# connectors.net
KiCad netlist of a schematic drawn in Altium Designer
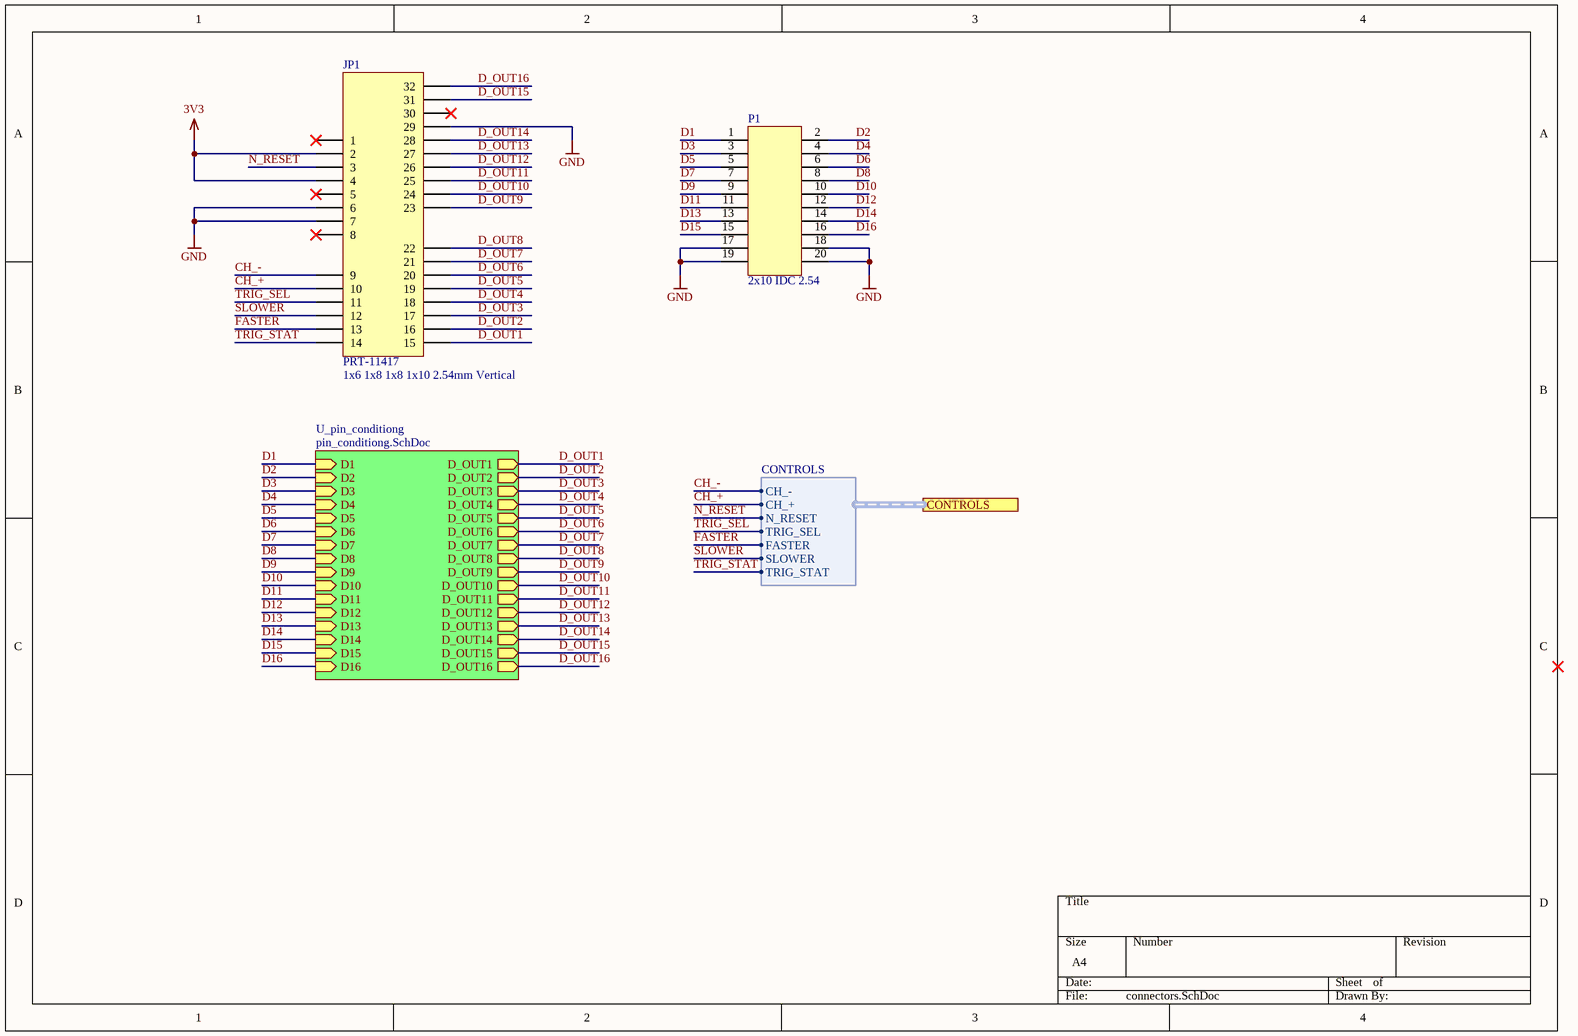
[diagram p0: connectors.SchDoc]

(export (version "E")
  (design (tool "Eeschema 10.0.6"))
  (components
    (comp (ref "JP1")
      (value "PRT-11417")
      (footprint "JP_ARDUINO_UNO_HEADER")
      (description "Header 6-Pin, 8-Pin, 8-Pin, 10-Pin")
      (fields
        (field (name "PART NUMBER") "JP_ARDUINO_UNO_HEADER_1x6_1x8_1x8_1x10_2.54")
        (field (name "SCH_FOOTPRINT") "1x6 1x8 1x8 1x10 2.54mm Vertical")
        (field (name "MANUFACTURER") "Sparkfun")
      )
      (libsource (lib "Library") (part "JP_ARDUINO_UNO_HEADER"))
    )
    (comp (ref "P1")
      (value "2x10 IDC 2.54")
      (footprint "J-LINK_20_pin_2.54")
      (libsource (lib "soldering_station") (part "Header_2x10_2.54_Shrouded"))
    )
  )
  (nets
    (net (code "2") (name "/CH_+") (class "Default")
      (node (ref "JP1") (pin "10") (pinfunction "10_10") (pintype "passive"))
    )
    (net (code "3") (name "/CH_-") (class "Default")
      (node (ref "JP1") (pin "9") (pinfunction "9_9") (pintype "passive"))
    )
    (net (code "4") (name "/D1") (class "Default") (node (ref "P1") (pin "1") (pintype "passive")))
    (net (code "5") (name "/D2") (class "Default") (node (ref "P1") (pin "2") (pintype "passive")))
    (net (code "6") (name "/D3") (class "Default") (node (ref "P1") (pin "3") (pintype "passive")))
    (net (code "7") (name "/D4") (class "Default") (node (ref "P1") (pin "4") (pintype "passive")))
    (net (code "8") (name "/D5") (class "Default") (node (ref "P1") (pin "5") (pintype "passive")))
    (net (code "9") (name "/D6") (class "Default") (node (ref "P1") (pin "6") (pintype "passive")))
    (net (code "10") (name "/D7") (class "Default") (node (ref "P1") (pin "7") (pintype "passive")))
    (net (code "11") (name "/D8") (class "Default") (node (ref "P1") (pin "8") (pintype "passive")))
    (net (code "12") (name "/D9") (class "Default") (node (ref "P1") (pin "9") (pintype "passive")))
    (net (code "13") (name "/D10") (class "Default") (node (ref "P1") (pin "10") (pintype "passive")))
    (net (code "14") (name "/D11") (class "Default") (node (ref "P1") (pin "11") (pintype "passive")))
    (net (code "15") (name "/D12") (class "Default") (node (ref "P1") (pin "12") (pintype "passive")))
    (net (code "16") (name "/D13") (class "Default") (node (ref "P1") (pin "13") (pintype "passive")))
    (net (code "17") (name "/D14") (class "Default") (node (ref "P1") (pin "14") (pintype "passive")))
    (net (code "18") (name "/D15") (class "Default") (node (ref "P1") (pin "15") (pintype "passive")))
    (net (code "19") (name "/D16") (class "Default") (node (ref "P1") (pin "16") (pintype "passive")))
    (net (code "20") (name "/D_OUT1") (class "Default")
      (node (ref "JP1") (pin "15") (pinfunction "15_15") (pintype "passive"))
    )
    (net (code "21") (name "/D_OUT2") (class "Default")
      (node (ref "JP1") (pin "16") (pinfunction "16_16") (pintype "passive"))
    )
    (net (code "22") (name "/D_OUT3") (class "Default")
      (node (ref "JP1") (pin "17") (pinfunction "17_17") (pintype "passive"))
    )
    (net (code "23") (name "/D_OUT4") (class "Default")
      (node (ref "JP1") (pin "18") (pinfunction "18_18") (pintype "passive"))
    )
    (net (code "24") (name "/D_OUT5") (class "Default")
      (node (ref "JP1") (pin "19") (pinfunction "19_19") (pintype "passive"))
    )
    (net (code "25") (name "/D_OUT6") (class "Default")
      (node (ref "JP1") (pin "20") (pinfunction "20_20") (pintype "passive"))
    )
    (net (code "26") (name "/D_OUT7") (class "Default")
      (node (ref "JP1") (pin "21") (pinfunction "21_21") (pintype "passive"))
    )
    (net (code "27") (name "/D_OUT8") (class "Default")
      (node (ref "JP1") (pin "22") (pinfunction "22_22") (pintype "passive"))
    )
    (net (code "28") (name "/D_OUT9") (class "Default")
      (node (ref "JP1") (pin "23") (pinfunction "23_23") (pintype "passive"))
    )
    (net (code "29") (name "/D_OUT10") (class "Default")
      (node (ref "JP1") (pin "24") (pinfunction "24_24") (pintype "passive"))
    )
    (net (code "30") (name "/D_OUT11") (class "Default")
      (node (ref "JP1") (pin "25") (pinfunction "25_25") (pintype "passive"))
    )
    (net (code "31") (name "/D_OUT12") (class "Default")
      (node (ref "JP1") (pin "26") (pinfunction "26_26") (pintype "passive"))
    )
    (net (code "32") (name "/D_OUT13") (class "Default")
      (node (ref "JP1") (pin "27") (pinfunction "27_27") (pintype "passive"))
    )
    (net (code "33") (name "/D_OUT14") (class "Default")
      (node (ref "JP1") (pin "28") (pinfunction "28_28") (pintype "passive"))
    )
    (net (code "34") (name "/D_OUT15") (class "Default")
      (node (ref "JP1") (pin "31") (pinfunction "31_31") (pintype "passive"))
    )
    (net (code "35") (name "/D_OUT16") (class "Default")
      (node (ref "JP1") (pin "32") (pinfunction "32_32") (pintype "passive"))
    )
    (net (code "36") (name "/FASTER") (class "Default")
      (node (ref "JP1") (pin "13") (pinfunction "13_13") (pintype "passive"))
    )
    (net (code "37") (name "/N_RESET") (class "Default")
      (node (ref "JP1") (pin "3") (pinfunction "3_3") (pintype "passive"))
    )
    (net (code "38") (name "/SLOWER") (class "Default")
      (node (ref "JP1") (pin "12") (pinfunction "12_12") (pintype "passive"))
    )
    (net (code "39") (name "/TRIG_SEL") (class "Default")
      (node (ref "JP1") (pin "11") (pinfunction "11_11") (pintype "passive"))
    )
    (net (code "40") (name "/TRIG_STAT") (class "Default")
      (node (ref "JP1") (pin "14") (pinfunction "14_14") (pintype "passive"))
    )
    (net (code "42") (name "3V3") (class "Default")
      (node (ref "JP1") (pin "2") (pinfunction "2_2") (pintype "passive"))
      (node (ref "JP1") (pin "4") (pinfunction "4_4") (pintype "passive"))
    )
    (net (code "43") (name "GND") (class "Default")
      (node (ref "JP1") (pin "29") (pinfunction "29_29") (pintype "passive"))
      (node (ref "JP1") (pin "6") (pinfunction "6_6") (pintype "passive"))
      (node (ref "JP1") (pin "7") (pinfunction "7_7") (pintype "passive"))
      (node (ref "P1") (pin "17") (pintype "passive"))
      (node (ref "P1") (pin "18") (pintype "passive"))
      (node (ref "P1") (pin "19") (pintype "passive"))
      (node (ref "P1") (pin "20") (pintype "passive"))
    )
    (net (code "44") (name "unconnected-(JP1-Pad1)") (class "Default")
      (node (ref "JP1") (pin "1") (pinfunction "1_1") (pintype "passive+no_connect"))
    )
    (net (code "45") (name "unconnected-(JP1-Pad5)") (class "Default")
      (node (ref "JP1") (pin "5") (pinfunction "5_5") (pintype "passive+no_connect"))
    )
    (net (code "46") (name "unconnected-(JP1-Pad8)") (class "Default")
      (node (ref "JP1") (pin "8") (pinfunction "8_8") (pintype "passive+no_connect"))
    )
    (net (code "47") (name "unconnected-(JP1-Pad30)") (class "Default")
      (node (ref "JP1") (pin "30") (pinfunction "30_30") (pintype "passive+no_connect"))
    )
  )
)
